# Sheet1.net
KiCad netlist of a schematic drawn in Altium Designer
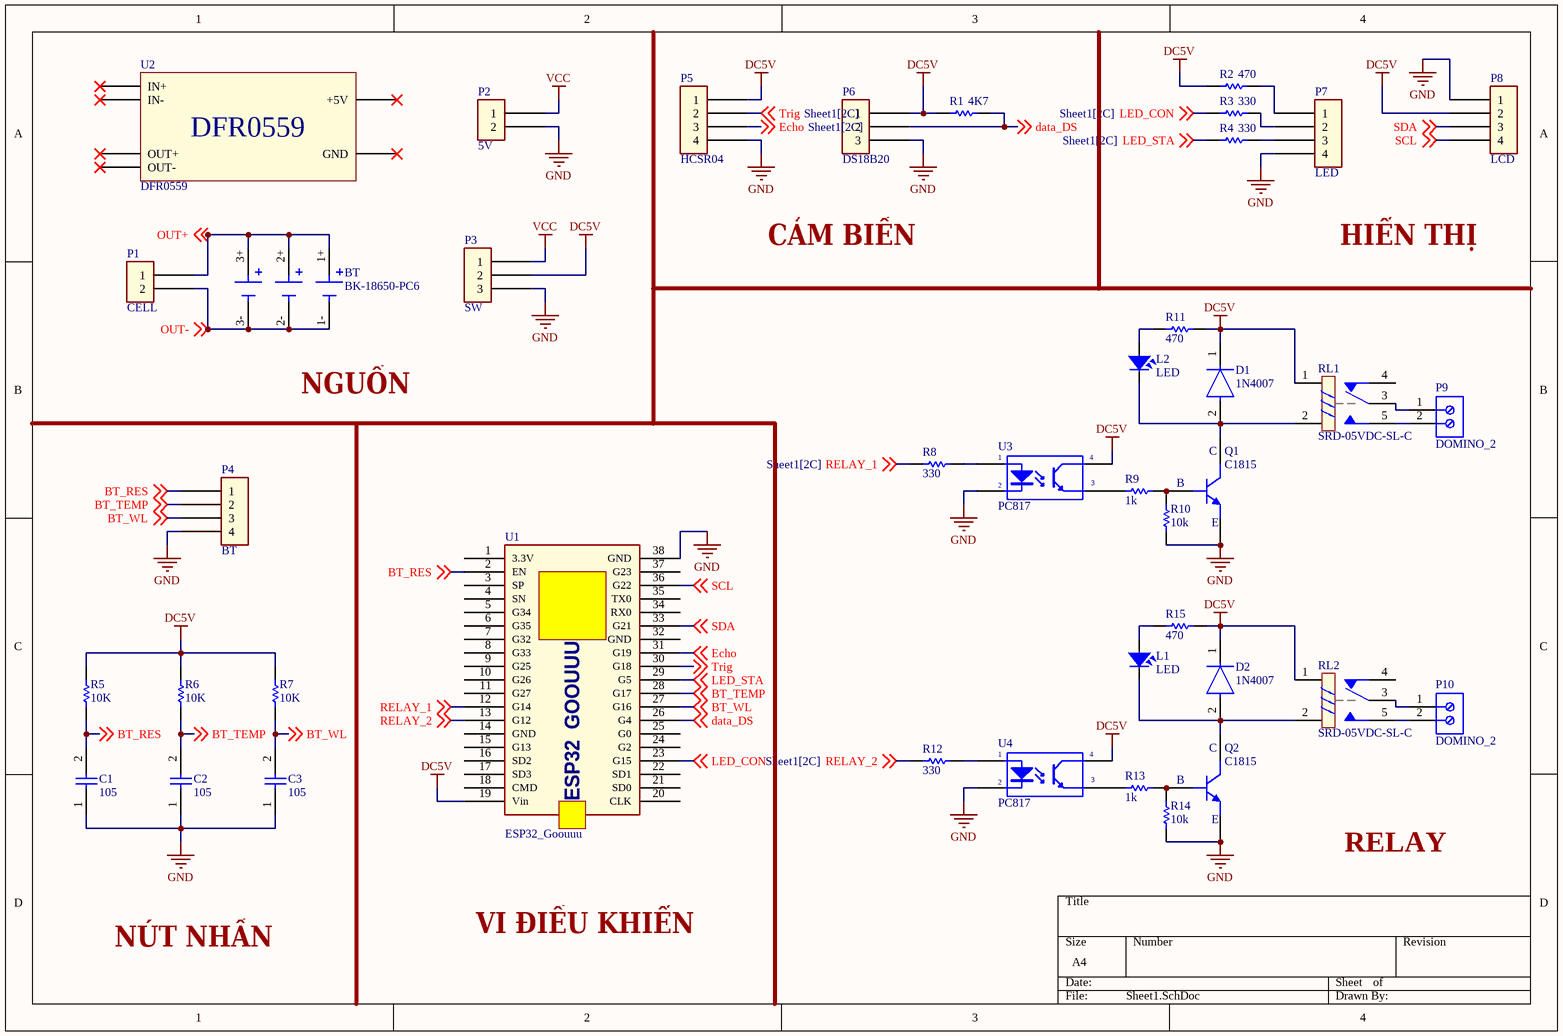
[diagram p0: Sheet1.SchDoc]

(export (version "E")
  (design (tool "Eeschema 10.0.6"))
  (components
    (comp (ref "BT")
      (value "BK-18650-PC6")
      (footprint "BAT_BK-18650-PC6")
      (description "Battery Holder _Open_ 18650 3 Cell PC Pin")
      (fields (field (name "MF") "MPD"))
      (libsource (lib "SachTran_Lib") (part "BK-18650-PC6"))
    )
    (comp (ref "C1")
      (value "105")
      (footprint "CAP_CER_105")
      (description "Capacitor Ceramic 105 1uF")
      (libsource (lib "SachTran_Lib") (part "CAP_CER_105"))
    )
    (comp (ref "C2")
      (value "105")
      (footprint "CAP_CER_105")
      (description "Capacitor Ceramic 105 1uF")
      (libsource (lib "SachTran_Lib") (part "CAP_CER_105"))
    )
    (comp (ref "C3")
      (value "105")
      (footprint "CAP_CER_105")
      (description "Capacitor Ceramic 105 1uF")
      (libsource (lib "SachTran_Lib") (part "CAP_CER_105"))
    )
    (comp (ref "D1")
      (value "1N4007")
      (footprint "DO-41")
      (description "Diode 1N4007 DO-41, 1000V, 1.00A")
      (fields (field (name "MANUFACTURER") "Diotec"))
      (libsource (lib "SachTran_Lib") (part "1N4007"))
    )
    (comp (ref "D2")
      (value "1N4007")
      (footprint "DO-41")
      (description "Diode 1N4007 DO-41, 1000V, 1.00A")
      (fields (field (name "MANUFACTURER") "Diotec"))
      (libsource (lib "SachTran_Lib") (part "1N4007"))
    )
    (comp (ref "L1") (value "LED") (footprint "LED-5-RED") (libsource (lib "SachTran_Lib") (part "LED")))
    (comp (ref "L2") (value "LED") (footprint "LED-5-RED") (libsource (lib "SachTran_Lib") (part "LED")))
    (comp (ref "P1")
      (value "CELL")
      (footprint "CON2")
      (description "Connector 2")
      (libsource (lib "SachTran_Lib") (part "CON2"))
    )
    (comp (ref "P2")
      (value "5V")
      (footprint "CON2")
      (description "Connector 2")
      (libsource (lib "SachTran_Lib") (part "CON2"))
    )
    (comp (ref "P3")
      (value "SW")
      (footprint "CON3")
      (description "Connector 3")
      (libsource (lib "SachTran_Lib") (part "CON3"))
    )
    (comp (ref "P4")
      (value "BT")
      (footprint "CON4")
      (description "Connector 4")
      (libsource (lib "SachTran_Lib") (part "CON4"))
    )
    (comp (ref "P5")
      (value "HCSR04")
      (footprint "CON4")
      (description "Connector 4")
      (libsource (lib "") (part "CON4_1"))
    )
    (comp (ref "P6")
      (value "DS18B20")
      (footprint "CON3")
      (description "Connector 3")
      (libsource (lib "SachTran_Lib") (part "CON3"))
    )
    (comp (ref "P7")
      (value "LED")
      (footprint "CON4")
      (description "Connector 4")
      (libsource (lib "SachTran_Lib") (part "CON4"))
    )
    (comp (ref "P8")
      (value "LCD")
      (footprint "CON4")
      (description "Connector 4")
      (libsource (lib "SachTran_Lib") (part "CON4"))
    )
    (comp (ref "P9")
      (value "DOMINO_2")
      (footprint "DOMINO_2")
      (description "Domino 2")
      (libsource (lib "SachTran_Lib") (part "DOMINO_2"))
    )
    (comp (ref "P10")
      (value "DOMINO_2")
      (footprint "DOMINO_2")
      (description "Domino 2")
      (libsource (lib "SachTran_Lib") (part "DOMINO_2"))
    )
    (comp (ref "Q1")
      (value "C1815")
      (footprint "QTO-92")
      (description "NPN 600mW, ECB")
      (libsource (lib "SachTran_Lib") (part "C1815"))
    )
    (comp (ref "Q2")
      (value "C1815")
      (footprint "QTO-92")
      (description "NPN 600mW, ECB")
      (libsource (lib "SachTran_Lib") (part "C1815"))
    )
    (comp (ref "R1")
      (value "4K7")
      (footprint "R1/4W")
      (description "Resistor Through-Hole  1K 1/4W")
      (fields (field (name "Comment") "RES"))
      (libsource (lib "SachTran_Lib") (part "RES_1K_1/4W"))
    )
    (comp (ref "R2")
      (value "470")
      (footprint "R1/4W")
      (description "Resistor Through-Hole  1K 1/4W")
      (fields (field (name "Comment") "RES"))
      (libsource (lib "SachTran_Lib") (part "RES_1K_1/4W"))
    )
    (comp (ref "R3")
      (value "330")
      (footprint "R1/4W")
      (description "Resistor Through-Hole  1K 1/4W")
      (fields (field (name "Comment") "RES"))
      (libsource (lib "SachTran_Lib") (part "RES_1K_1/4W"))
    )
    (comp (ref "R4")
      (value "330")
      (footprint "R1/4W")
      (description "Resistor Through-Hole  1K 1/4W")
      (fields (field (name "Comment") "RES"))
      (libsource (lib "SachTran_Lib") (part "RES_1K_1/4W"))
    )
    (comp (ref "R5")
      (value "10K")
      (footprint "R1/4W")
      (description "Resistor Through-Hole  1K 1/4W")
      (fields (field (name "Comment") "RES"))
      (libsource (lib "SachTran_Lib") (part "RES_1K_1/4W"))
    )
    (comp (ref "R6")
      (value "10K")
      (footprint "R1/4W")
      (description "Resistor Through-Hole  1K 1/4W")
      (fields (field (name "Comment") "RES"))
      (libsource (lib "SachTran_Lib") (part "RES_1K_1/4W"))
    )
    (comp (ref "R7")
      (value "10K")
      (footprint "R1/4W")
      (description "Resistor Through-Hole  1K 1/4W")
      (fields (field (name "Comment") "RES"))
      (libsource (lib "SachTran_Lib") (part "RES_1K_1/4W"))
    )
    (comp (ref "R8")
      (value "330")
      (footprint "R1/4W")
      (description "Resistor Through-Hole  1K 1/4W")
      (fields (field (name "Comment") "RES"))
      (libsource (lib "SachTran_Lib") (part "RES_1K_1/4W"))
    )
    (comp (ref "R9")
      (value "1k")
      (footprint "R1/4W")
      (description "Resistor Through-Hole  1K 1/4W")
      (fields (field (name "Comment") "RES"))
      (libsource (lib "SachTran_Lib") (part "RES_1K_1/4W"))
    )
    (comp (ref "R10")
      (value "10k")
      (footprint "R1/4W")
      (description "Resistor Through-Hole  1K 1/4W")
      (fields (field (name "Comment") "RES"))
      (libsource (lib "SachTran_Lib") (part "RES_1K_1/4W"))
    )
    (comp (ref "R11")
      (value "470")
      (footprint "R1/4W")
      (description "Resistor Through-Hole  1K 1/4W")
      (fields (field (name "Comment") "RES"))
      (libsource (lib "SachTran_Lib") (part "RES_1K_1/4W"))
    )
    (comp (ref "R12")
      (value "330")
      (footprint "R1/4W")
      (description "Resistor Through-Hole  1K 1/4W")
      (fields (field (name "Comment") "RES"))
      (libsource (lib "SachTran_Lib") (part "RES_1K_1/4W"))
    )
    (comp (ref "R13")
      (value "1k")
      (footprint "R1/4W")
      (description "Resistor Through-Hole  1K 1/4W")
      (fields (field (name "Comment") "RES"))
      (libsource (lib "SachTran_Lib") (part "RES_1K_1/4W"))
    )
    (comp (ref "R14")
      (value "10k")
      (footprint "R1/4W")
      (description "Resistor Through-Hole  1K 1/4W")
      (fields (field (name "Comment") "RES"))
      (libsource (lib "SachTran_Lib") (part "RES_1K_1/4W"))
    )
    (comp (ref "R15")
      (value "470")
      (footprint "R1/4W")
      (description "Resistor Through-Hole  1K 1/4W")
      (fields (field (name "Comment") "RES"))
      (libsource (lib "SachTran_Lib") (part "RES_1K_1/4W"))
    )
    (comp (ref "RL1")
      (value "SRD-05VDC-SL-C")
      (footprint "SRD-05VDC-SL-C")
      (libsource (lib "SachTran_Lib") (part "SRD-05VDC-SL-C"))
    )
    (comp (ref "RL2")
      (value "SRD-05VDC-SL-C")
      (footprint "SRD-05VDC-SL-C")
      (libsource (lib "SachTran_Lib") (part "SRD-05VDC-SL-C"))
    )
    (comp (ref "U1")
      (value "ESP32_Goouuu")
      (footprint "ESP32_Goouuu")
      (libsource (lib "SachTran_Lib") (part "ESP32_Goouuu"))
    )
    (comp (ref "U2")
      (value "DFR0559")
      (footprint "DFR0559")
      (libsource (lib "SachTran_Lib") (part "DFR0559"))
    )
    (comp (ref "U3")
      (value "PC817")
      (footprint "PC817-DIP4")
      (description "PC817 DIP Single Opto")
      (libsource (lib "SachTran_Lib") (part "PC817 DIP"))
    )
    (comp (ref "U4")
      (value "PC817")
      (footprint "PC817-DIP4")
      (description "PC817 DIP Single Opto")
      (libsource (lib "SachTran_Lib") (part "PC817 DIP"))
    )
  )
  (nets
    (net (code "1") (name "BT_RES") (class "Default")
      (node (ref "C1") (pin "2") (pinfunction "2_2") (pintype "passive"))
      (node (ref "P4") (pin "1") (pinfunction "1_1") (pintype "passive"))
      (node (ref "R5") (pin "2") (pinfunction "2_2") (pintype "passive"))
      (node (ref "U1") (pin "2") (pinfunction "EN_2") (pintype "passive"))
    )
    (net (code "2") (name "BT_TEMP") (class "Default")
      (node (ref "C2") (pin "2") (pinfunction "2_2") (pintype "passive"))
      (node (ref "P4") (pin "2") (pinfunction "2_2") (pintype "passive"))
      (node (ref "R6") (pin "2") (pinfunction "2_2") (pintype "passive"))
      (node (ref "U1") (pin "28") (pinfunction "G17_28") (pintype "passive"))
    )
    (net (code "3") (name "BT_WL") (class "Default")
      (node (ref "C3") (pin "2") (pinfunction "2_2") (pintype "passive"))
      (node (ref "P4") (pin "3") (pinfunction "3_3") (pintype "passive"))
      (node (ref "R7") (pin "2") (pinfunction "2_2") (pintype "passive"))
      (node (ref "U1") (pin "27") (pinfunction "G16_27") (pintype "passive"))
    )
    (net (code "4") (name "DC5V") (class "Default")
      (node (ref "D1") (pin "1") (pinfunction "C_1") (pintype "passive"))
      (node (ref "D2") (pin "1") (pinfunction "C_1") (pintype "passive"))
      (node (ref "P3") (pin "2") (pinfunction "2_2") (pintype "passive"))
      (node (ref "P5") (pin "1") (pinfunction "1_1") (pintype "passive"))
      (node (ref "P6") (pin "1") (pinfunction "1_1") (pintype "passive"))
      (node (ref "P8") (pin "2") (pinfunction "2_2") (pintype "passive"))
      (node (ref "R1") (pin "2") (pinfunction "2_2") (pintype "passive"))
      (node (ref "R11") (pin "2") (pinfunction "2_2") (pintype "passive"))
      (node (ref "R15") (pin "2") (pinfunction "2_2") (pintype "passive"))
      (node (ref "R2") (pin "2") (pinfunction "2_2") (pintype "passive"))
      (node (ref "R5") (pin "1") (pinfunction "1_1") (pintype "passive"))
      (node (ref "R6") (pin "1") (pinfunction "1_1") (pintype "passive"))
      (node (ref "R7") (pin "1") (pinfunction "1_1") (pintype "passive"))
      (node (ref "RL1") (pin "1") (pinfunction "1_1") (pintype "passive"))
      (node (ref "RL2") (pin "1") (pinfunction "1_1") (pintype "passive"))
      (node (ref "U1") (pin "19") (pinfunction "Vin_19") (pintype "passive"))
      (node (ref "U3") (pin "4") (pinfunction "C_4") (pintype "passive"))
      (node (ref "U4") (pin "4") (pinfunction "C_4") (pintype "passive"))
    )
    (net (code "5") (name "Echo") (class "Default")
      (node (ref "P5") (pin "3") (pinfunction "3_3") (pintype "passive"))
      (node (ref "U1") (pin "31") (pinfunction "G19_31") (pintype "passive"))
    )
    (net (code "6") (name "GND") (class "Default")
      (node (ref "C1") (pin "1") (pinfunction "1_1") (pintype "passive"))
      (node (ref "C2") (pin "1") (pinfunction "1_1") (pintype "passive"))
      (node (ref "C3") (pin "1") (pinfunction "1_1") (pintype "passive"))
      (node (ref "P2") (pin "2") (pinfunction "2_2") (pintype "passive"))
      (node (ref "P3") (pin "3") (pinfunction "3_3") (pintype "passive"))
      (node (ref "P4") (pin "4") (pinfunction "4_4") (pintype "passive"))
      (node (ref "P5") (pin "4") (pinfunction "4_4") (pintype "passive"))
      (node (ref "P6") (pin "3") (pinfunction "3_3") (pintype "passive"))
      (node (ref "P7") (pin "4") (pinfunction "4_4") (pintype "passive"))
      (node (ref "P8") (pin "1") (pinfunction "1_1") (pintype "passive"))
      (node (ref "Q1") (pin "1") (pinfunction "E_1") (pintype "passive"))
      (node (ref "Q2") (pin "1") (pinfunction "E_1") (pintype "passive"))
      (node (ref "R10") (pin "1") (pinfunction "1_1") (pintype "passive"))
      (node (ref "R14") (pin "1") (pinfunction "1_1") (pintype "passive"))
      (node (ref "U1") (pin "38") (pinfunction "GND_38") (pintype "passive"))
      (node (ref "U3") (pin "2") (pinfunction "K_2") (pintype "passive"))
      (node (ref "U4") (pin "2") (pinfunction "K_2") (pintype "passive"))
    )
    (net (code "7") (name "LED_CON") (class "Default")
      (node (ref "R3") (pin "2") (pinfunction "2_2") (pintype "passive"))
      (node (ref "U1") (pin "23") (pinfunction "G15_23") (pintype "passive"))
    )
    (net (code "8") (name "LED_STA") (class "Default")
      (node (ref "R4") (pin "2") (pinfunction "2_2") (pintype "passive"))
      (node (ref "U1") (pin "29") (pinfunction "G5_29") (pintype "passive"))
    )
    (net (code "9") (name "Net-(D1-A)") (class "Default")
      (node (ref "D1") (pin "2") (pinfunction "A_2") (pintype "passive"))
      (node (ref "L2") (pin "2") (pinfunction "2_2") (pintype "passive"))
      (node (ref "Q1") (pin "2") (pinfunction "C_2") (pintype "passive"))
      (node (ref "RL1") (pin "2") (pinfunction "2_2") (pintype "passive"))
    )
    (net (code "10") (name "Net-(D2-A)") (class "Default")
      (node (ref "D2") (pin "2") (pinfunction "A_2") (pintype "passive"))
      (node (ref "L1") (pin "2") (pinfunction "2_2") (pintype "passive"))
      (node (ref "Q2") (pin "2") (pinfunction "C_2") (pintype "passive"))
      (node (ref "RL2") (pin "2") (pinfunction "2_2") (pintype "passive"))
    )
    (net (code "11") (name "Net-(L1-Pad1)") (class "Default")
      (node (ref "L1") (pin "1") (pinfunction "1_1") (pintype "passive"))
      (node (ref "R15") (pin "1") (pinfunction "1_1") (pintype "passive"))
    )
    (net (code "12") (name "Net-(L2-Pad1)") (class "Default")
      (node (ref "L2") (pin "1") (pinfunction "1_1") (pintype "passive"))
      (node (ref "R11") (pin "1") (pinfunction "1_1") (pintype "passive"))
    )
    (net (code "13") (name "Net-(P7-Pad1)") (class "Default")
      (node (ref "P7") (pin "1") (pinfunction "1_1") (pintype "passive"))
      (node (ref "R2") (pin "1") (pinfunction "1_1") (pintype "passive"))
    )
    (net (code "14") (name "Net-(P7-Pad2)") (class "Default")
      (node (ref "P7") (pin "2") (pinfunction "2_2") (pintype "passive"))
      (node (ref "R3") (pin "1") (pinfunction "1_1") (pintype "passive"))
    )
    (net (code "15") (name "Net-(P7-Pad3)") (class "Default")
      (node (ref "P7") (pin "3") (pinfunction "3_3") (pintype "passive"))
      (node (ref "R4") (pin "1") (pinfunction "1_1") (pintype "passive"))
    )
    (net (code "16") (name "Net-(P9-Pad1)") (class "Default")
      (node (ref "P9") (pin "1") (pinfunction "1_1") (pintype "passive"))
      (node (ref "RL1") (pin "3") (pinfunction "3_3") (pintype "passive"))
    )
    (net (code "17") (name "Net-(P9-Pad2)") (class "Default")
      (node (ref "P9") (pin "2") (pinfunction "2_2") (pintype "passive"))
      (node (ref "RL1") (pin "5") (pinfunction "5_5") (pintype "passive"))
    )
    (net (code "18") (name "Net-(P10-Pad1)") (class "Default")
      (node (ref "P10") (pin "1") (pinfunction "1_1") (pintype "passive"))
      (node (ref "RL2") (pin "3") (pinfunction "3_3") (pintype "passive"))
    )
    (net (code "19") (name "Net-(P10-Pad2)") (class "Default")
      (node (ref "P10") (pin "2") (pinfunction "2_2") (pintype "passive"))
      (node (ref "RL2") (pin "5") (pinfunction "5_5") (pintype "passive"))
    )
    (net (code "20") (name "Net-(Q1-B)") (class "Default")
      (node (ref "Q1") (pin "3") (pinfunction "B_3") (pintype "passive"))
      (node (ref "R10") (pin "2") (pinfunction "2_2") (pintype "passive"))
      (node (ref "R9") (pin "2") (pinfunction "2_2") (pintype "passive"))
    )
    (net (code "21") (name "Net-(Q2-B)") (class "Default")
      (node (ref "Q2") (pin "3") (pinfunction "B_3") (pintype "passive"))
      (node (ref "R13") (pin "2") (pinfunction "2_2") (pintype "passive"))
      (node (ref "R14") (pin "2") (pinfunction "2_2") (pintype "passive"))
    )
    (net (code "22") (name "Net-(U3-A)") (class "Default")
      (node (ref "R8") (pin "2") (pinfunction "2_2") (pintype "passive"))
      (node (ref "U3") (pin "1") (pinfunction "A_1") (pintype "passive"))
    )
    (net (code "23") (name "Net-(U3-E)") (class "Default")
      (node (ref "R9") (pin "1") (pinfunction "1_1") (pintype "passive"))
      (node (ref "U3") (pin "3") (pinfunction "E_3") (pintype "passive"))
    )
    (net (code "24") (name "Net-(U4-A)") (class "Default")
      (node (ref "R12") (pin "2") (pinfunction "2_2") (pintype "passive"))
      (node (ref "U4") (pin "1") (pinfunction "A_1") (pintype "passive"))
    )
    (net (code "25") (name "Net-(U4-E)") (class "Default")
      (node (ref "R13") (pin "1") (pinfunction "1_1") (pintype "passive"))
      (node (ref "U4") (pin "3") (pinfunction "E_3") (pintype "passive"))
    )
    (net (code "26") (name "OUT+") (class "Default")
      (node (ref "BT") (pin "1+") (pinfunction "1+_1+") (pintype "passive"))
      (node (ref "BT") (pin "2+") (pinfunction "2+_2+") (pintype "passive"))
      (node (ref "BT") (pin "3+") (pinfunction "3+_3+") (pintype "passive"))
      (node (ref "P1") (pin "1") (pinfunction "1_1") (pintype "passive"))
    )
    (net (code "27") (name "OUT-") (class "Default")
      (node (ref "BT") (pin "1-") (pinfunction "1-_1-") (pintype "passive"))
      (node (ref "BT") (pin "2-") (pinfunction "2-_2-") (pintype "passive"))
      (node (ref "BT") (pin "3-") (pinfunction "3-_3-") (pintype "passive"))
      (node (ref "P1") (pin "2") (pinfunction "2_2") (pintype "passive"))
    )
    (net (code "28") (name "RELAY_1") (class "Default")
      (node (ref "R8") (pin "1") (pinfunction "1_1") (pintype "passive"))
      (node (ref "U1") (pin "12") (pinfunction "G14_12") (pintype "passive"))
    )
    (net (code "29") (name "RELAY_2") (class "Default")
      (node (ref "R12") (pin "1") (pinfunction "1_1") (pintype "passive"))
      (node (ref "U1") (pin "13") (pinfunction "G12_13") (pintype "passive"))
    )
    (net (code "30") (name "SCL") (class "Default")
      (node (ref "P8") (pin "4") (pinfunction "4_4") (pintype "passive"))
      (node (ref "U1") (pin "36") (pinfunction "G22_36") (pintype "passive"))
    )
    (net (code "31") (name "SDA") (class "Default")
      (node (ref "P8") (pin "3") (pinfunction "3_3") (pintype "passive"))
      (node (ref "U1") (pin "33") (pinfunction "G21_33") (pintype "passive"))
    )
    (net (code "32") (name "Trig") (class "Default")
      (node (ref "P5") (pin "2") (pinfunction "2_2") (pintype "passive"))
      (node (ref "U1") (pin "30") (pinfunction "G18_30") (pintype "passive"))
    )
    (net (code "33") (name "VCC") (class "Default")
      (node (ref "P2") (pin "1") (pinfunction "1_1") (pintype "passive"))
      (node (ref "P3") (pin "1") (pinfunction "1_1") (pintype "passive"))
    )
    (net (code "34") (name "data_DS") (class "Default")
      (node (ref "P6") (pin "2") (pinfunction "2_2") (pintype "passive"))
      (node (ref "R1") (pin "1") (pinfunction "1_1") (pintype "passive"))
      (node (ref "U1") (pin "26") (pinfunction "G4_26") (pintype "passive"))
    )
    (net (code "35") (name "unconnected-(RL1-Pad4)") (class "Default")
      (node (ref "RL1") (pin "4") (pinfunction "4_4") (pintype "passive"))
    )
    (net (code "36") (name "unconnected-(RL2-Pad4)") (class "Default")
      (node (ref "RL2") (pin "4") (pinfunction "4_4") (pintype "passive"))
    )
    (net (code "37") (name "unconnected-(U1-3.3V-Pad1)") (class "Default")
      (node (ref "U1") (pin "1") (pinfunction "3.3V_1") (pintype "passive"))
    )
    (net (code "38") (name "unconnected-(U1-CLK-Pad20)") (class "Default")
      (node (ref "U1") (pin "20") (pinfunction "CLK_20") (pintype "passive"))
    )
    (net (code "39") (name "unconnected-(U1-CMD-Pad18)") (class "Default")
      (node (ref "U1") (pin "18") (pinfunction "CMD_18") (pintype "passive"))
    )
    (net (code "40") (name "unconnected-(U1-G0-Pad25)") (class "Default")
      (node (ref "U1") (pin "25") (pinfunction "G0_25") (pintype "passive"))
    )
    (net (code "41") (name "unconnected-(U1-G2-Pad24)") (class "Default")
      (node (ref "U1") (pin "24") (pinfunction "G2_24") (pintype "passive"))
    )
    (net (code "42") (name "unconnected-(U1-G13-Pad15)") (class "Default")
      (node (ref "U1") (pin "15") (pinfunction "G13_15") (pintype "passive"))
    )
    (net (code "43") (name "unconnected-(U1-G23-Pad37)") (class "Default")
      (node (ref "U1") (pin "37") (pinfunction "G23_37") (pintype "passive"))
    )
    (net (code "44") (name "unconnected-(U1-G25-Pad9)") (class "Default")
      (node (ref "U1") (pin "9") (pinfunction "G25_9") (pintype "passive"))
    )
    (net (code "45") (name "unconnected-(U1-G26-Pad10)") (class "Default")
      (node (ref "U1") (pin "10") (pinfunction "G26_10") (pintype "passive"))
    )
    (net (code "46") (name "unconnected-(U1-G27-Pad11)") (class "Default")
      (node (ref "U1") (pin "11") (pinfunction "G27_11") (pintype "passive"))
    )
    (net (code "47") (name "unconnected-(U1-G32-Pad7)") (class "Default")
      (node (ref "U1") (pin "7") (pinfunction "G32_7") (pintype "passive"))
    )
    (net (code "48") (name "unconnected-(U1-G33-Pad8)") (class "Default")
      (node (ref "U1") (pin "8") (pinfunction "G33_8") (pintype "passive"))
    )
    (net (code "49") (name "unconnected-(U1-G34-Pad5)") (class "Default")
      (node (ref "U1") (pin "5") (pinfunction "G34_5") (pintype "passive"))
    )
    (net (code "50") (name "unconnected-(U1-G35-Pad6)") (class "Default")
      (node (ref "U1") (pin "6") (pinfunction "G35_6") (pintype "passive"))
    )
    (net (code "51") (name "unconnected-(U1-GND-Pad14)") (class "Default")
      (node (ref "U1") (pin "14") (pinfunction "GND_14") (pintype "passive"))
    )
    (net (code "52") (name "unconnected-(U1-GND-Pad32)") (class "Default")
      (node (ref "U1") (pin "32") (pinfunction "GND_32") (pintype "passive"))
    )
    (net (code "53") (name "unconnected-(U1-RX0-Pad34)") (class "Default")
      (node (ref "U1") (pin "34") (pinfunction "RX0_34") (pintype "passive"))
    )
    (net (code "54") (name "unconnected-(U1-SD0-Pad21)") (class "Default")
      (node (ref "U1") (pin "21") (pinfunction "SD0_21") (pintype "passive"))
    )
    (net (code "55") (name "unconnected-(U1-SD1-Pad22)") (class "Default")
      (node (ref "U1") (pin "22") (pinfunction "SD1_22") (pintype "passive"))
    )
    (net (code "56") (name "unconnected-(U1-SD2-Pad16)") (class "Default")
      (node (ref "U1") (pin "16") (pinfunction "SD2_16") (pintype "passive"))
    )
    (net (code "57") (name "unconnected-(U1-SD3-Pad17)") (class "Default")
      (node (ref "U1") (pin "17") (pinfunction "SD3_17") (pintype "passive"))
    )
    (net (code "58") (name "unconnected-(U1-SN-Pad4)") (class "Default")
      (node (ref "U1") (pin "4") (pinfunction "SN_4") (pintype "passive"))
    )
    (net (code "59") (name "unconnected-(U1-SP-Pad3)") (class "Default")
      (node (ref "U1") (pin "3") (pinfunction "SP_3") (pintype "passive"))
    )
    (net (code "60") (name "unconnected-(U1-TX0-Pad35)") (class "Default")
      (node (ref "U1") (pin "35") (pinfunction "TX0_35") (pintype "passive"))
    )
    (net (code "61") (name "unconnected-(U2-+5V-Pad4)") (class "Default")
      (node (ref "U2") (pin "4") (pinfunction "+5V_4") (pintype "passive+no_connect"))
    )
    (net (code "62") (name "unconnected-(U2-GND-Pad3)") (class "Default")
      (node (ref "U2") (pin "3") (pinfunction "GND_3") (pintype "passive+no_connect"))
    )
    (net (code "63") (name "unconnected-(U2-IN+-Pad1)") (class "Default")
      (node (ref "U2") (pin "1") (pinfunction "IN+_1") (pintype "passive+no_connect"))
    )
    (net (code "64") (name "unconnected-(U2-IN--Pad2)") (class "Default")
      (node (ref "U2") (pin "2") (pinfunction "IN-_2") (pintype "passive+no_connect"))
    )
    (net (code "65") (name "unconnected-(U2-OUT+-Pad3)") (class "Default")
      (node (ref "U2") (pin "3") (pinfunction "OUT+_3") (pintype "passive+no_connect"))
    )
    (net (code "66") (name "unconnected-(U2-OUT--Pad4)") (class "Default")
      (node (ref "U2") (pin "4") (pinfunction "OUT-_4") (pintype "passive+no_connect"))
    )
  )
)
